# FMCWRadarv2.net
KiCad netlist of a schematic drawn in EAGLE
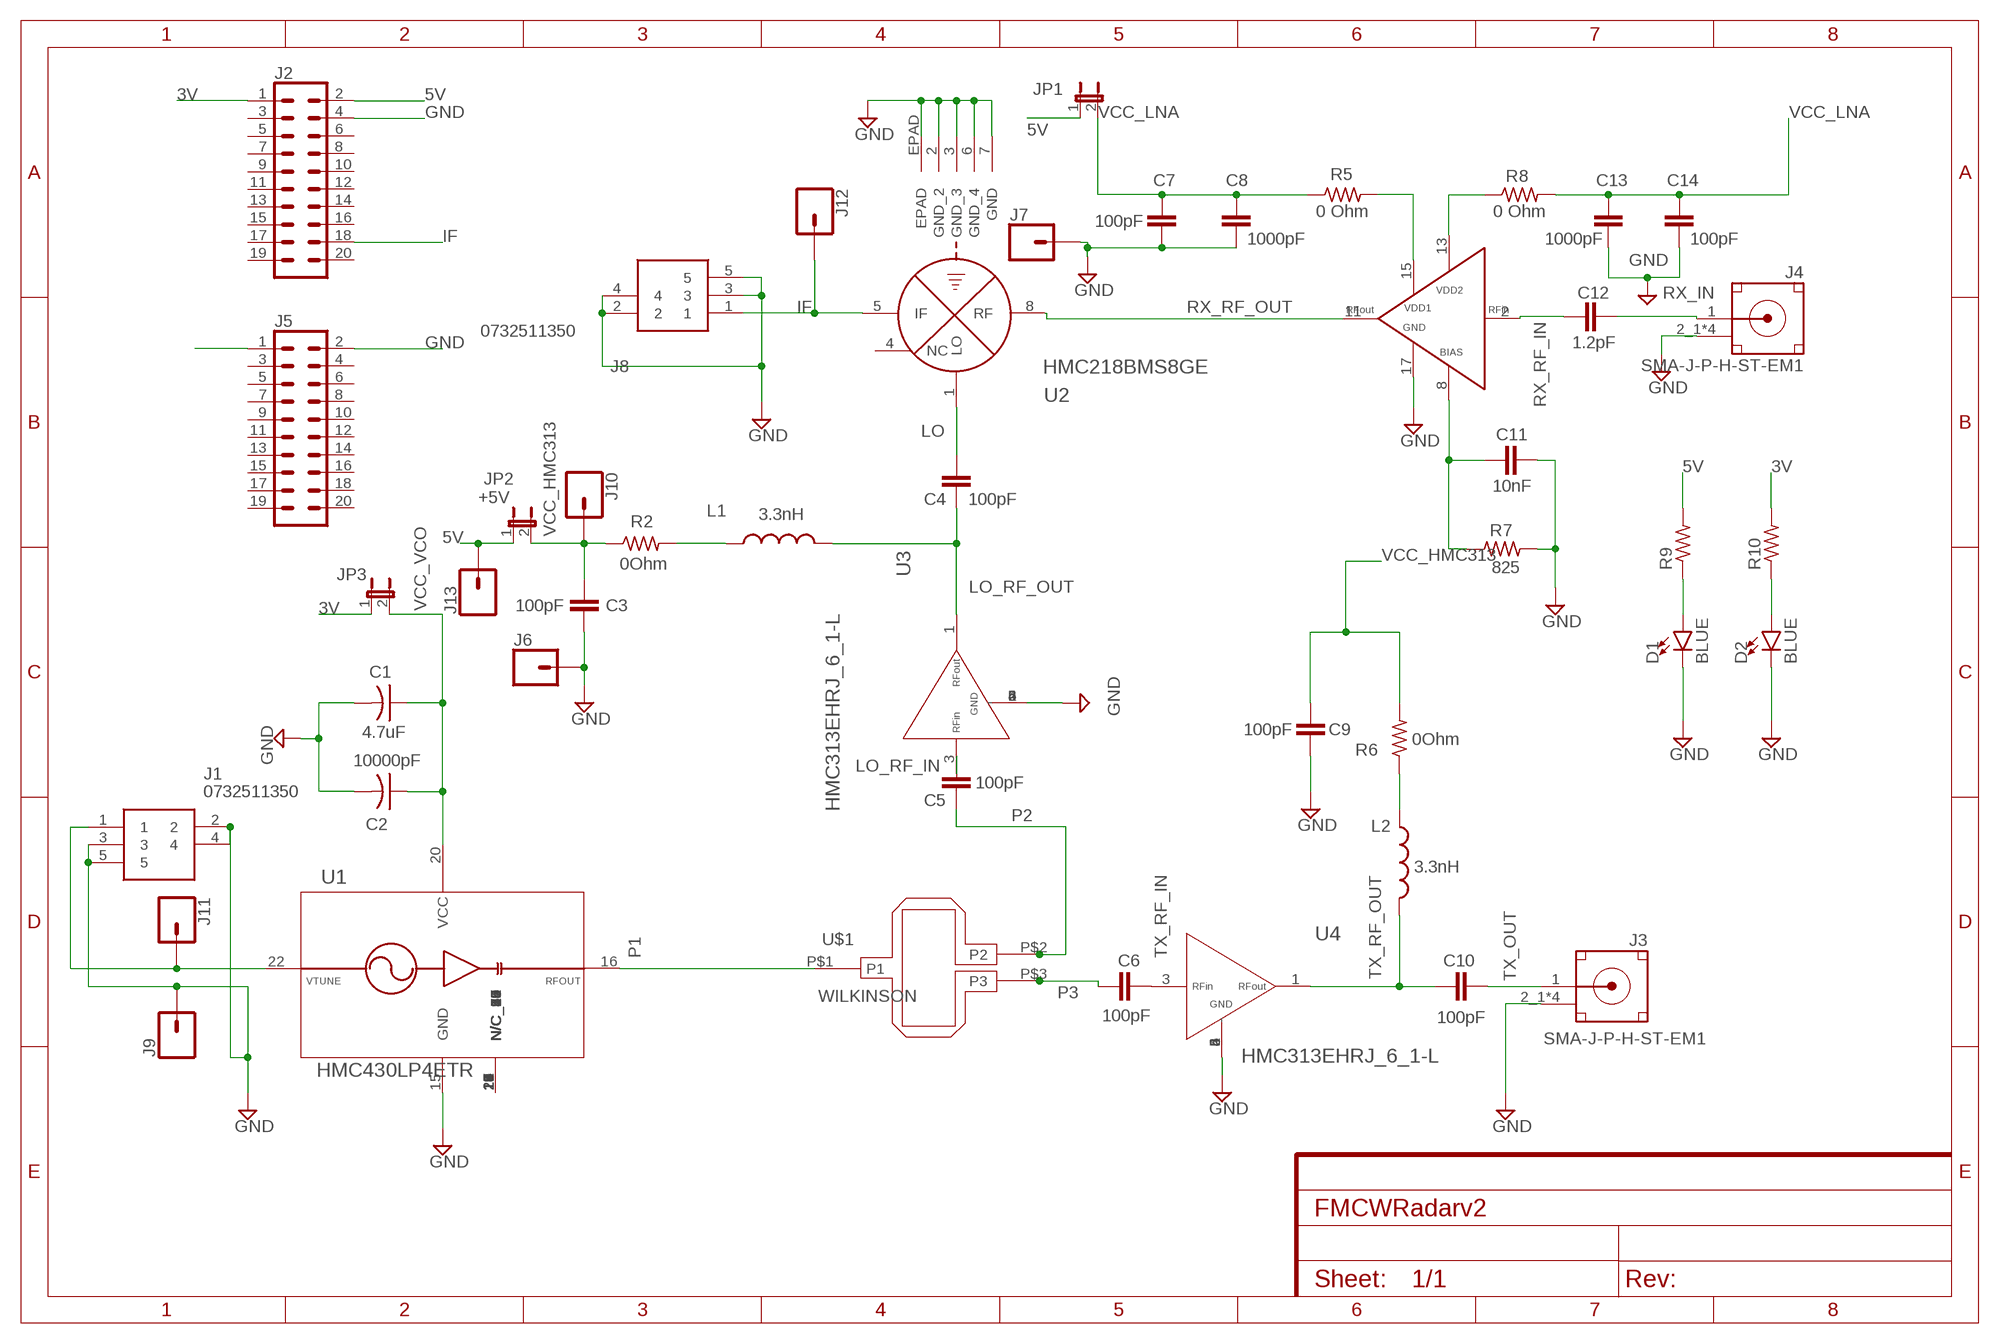
[diagram p0: schematic, sheet 1]

(export (version "E")
  (design (tool "Eeschema 10.0.6"))
  (components
    (comp (ref "C1")
      (value "4.7uF")
      (footprint "eagle-import:C0805")
      (libsource (lib "eagle-import") (part "C-USC0805"))
    )
    (comp (ref "C2")
      (value "10000pF")
      (footprint "eagle-import:C0603")
      (libsource (lib "eagle-import") (part "C-USC0603"))
    )
    (comp (ref "C3")
      (value "100pF")
      (footprint "eagle-import:C0805")
      (libsource (lib "eagle-import") (part "C-EUC0805"))
    )
    (comp (ref "C4")
      (value "100pF")
      (footprint "eagle-import:C0402")
      (libsource (lib "eagle-import") (part "C-EUC0402"))
    )
    (comp (ref "C5")
      (value "100pF")
      (footprint "eagle-import:C0402")
      (libsource (lib "eagle-import") (part "C-EUC0402"))
    )
    (comp (ref "C6")
      (value "100pF")
      (footprint "eagle-import:C0402")
      (libsource (lib "eagle-import") (part "C-EUC0402"))
    )
    (comp (ref "C7")
      (value "100pF")
      (footprint "eagle-import:C0603")
      (libsource (lib "eagle-import") (part "C-EUC0603"))
    )
    (comp (ref "C8")
      (value "1000pF")
      (footprint "eagle-import:C0603")
      (libsource (lib "eagle-import") (part "C-EUC0603"))
    )
    (comp (ref "C9")
      (value "100pF")
      (footprint "eagle-import:C0805")
      (libsource (lib "eagle-import") (part "C-EUC0805"))
    )
    (comp (ref "C10")
      (value "100pF")
      (footprint "eagle-import:C0402")
      (libsource (lib "eagle-import") (part "C-EUC0402"))
    )
    (comp (ref "C11")
      (value "10nF")
      (footprint "eagle-import:C0402")
      (libsource (lib "eagle-import") (part "C-EUC0402"))
    )
    (comp (ref "C12")
      (value "1.2pF")
      (footprint "eagle-import:C0402")
      (libsource (lib "eagle-import") (part "C-EUC0402"))
    )
    (comp (ref "C13")
      (value "1000pF")
      (footprint "eagle-import:C0603")
      (libsource (lib "eagle-import") (part "C-EUC0603"))
    )
    (comp (ref "C14")
      (value "100pF")
      (footprint "eagle-import:C0603")
      (libsource (lib "eagle-import") (part "C-EUC0603"))
    )
    (comp (ref "D1")
      (value "BLUE")
      (footprint "eagle-import:LED-1206")
      (libsource (lib "eagle-import") (part "LED-BLUE1206"))
    )
    (comp (ref "D2")
      (value "BLUE")
      (footprint "eagle-import:LED-1206")
      (libsource (lib "eagle-import") (part "LED-BLUE1206"))
    )
    (comp (ref "J1")
      (value "0732511350")
      (footprint "eagle-import:0732511350")
      (libsource (lib "eagle-import") (part "0732511350"))
    )
    (comp (ref "J2")
      (value "CONN_10X2")
      (footprint "eagle-import:2X10")
      (libsource (lib "eagle-import") (part "CONN_10X2"))
    )
    (comp (ref "J3")
      (value "SMA-J-P-H-ST-EM1")
      (footprint "eagle-import:SMA-J-P-H-ST-EM1")
      (fields (field (name "DIGI-KEY_PART_NUMBER") "SAM8857-ND") (field (name "MF") "Samtec"))
      (libsource (lib "eagle-import") (part "SMA-J-P-H-ST-EM1"))
    )
    (comp (ref "J4")
      (value "SMA-J-P-H-ST-EM1")
      (footprint "eagle-import:SMA-J-P-H-ST-EM1")
      (fields (field (name "DIGI-KEY_PART_NUMBER") "SAM8857-ND") (field (name "MF") "Samtec"))
      (libsource (lib "eagle-import") (part "SMA-J-P-H-ST-EM1"))
    )
    (comp (ref "J5")
      (value "CONN_10X2")
      (footprint "eagle-import:2X10")
      (libsource (lib "eagle-import") (part "CONN_10X2"))
    )
    (comp (ref "J6")
      (value "CONN_01")
      (footprint "eagle-import:1X01")
      (libsource (lib "eagle-import") (part "CONN_01"))
    )
    (comp (ref "J7")
      (value "CONN_01")
      (footprint "eagle-import:1X01")
      (libsource (lib "eagle-import") (part "CONN_01"))
    )
    (comp (ref "J8")
      (value "0732511350")
      (footprint "eagle-import:0732511350")
      (libsource (lib "eagle-import") (part "0732511350"))
    )
    (comp (ref "J9")
      (value "CONN_01")
      (footprint "eagle-import:1X01")
      (libsource (lib "eagle-import") (part "CONN_01"))
    )
    (comp (ref "J10")
      (value "CONN_01")
      (footprint "eagle-import:1X01")
      (libsource (lib "eagle-import") (part "CONN_01"))
    )
    (comp (ref "J11")
      (value "CONN_01")
      (footprint "eagle-import:1X01")
      (libsource (lib "eagle-import") (part "CONN_01"))
    )
    (comp (ref "J12")
      (value "CONN_01")
      (footprint "eagle-import:1X01")
      (libsource (lib "eagle-import") (part "CONN_01"))
    )
    (comp (ref "J13")
      (value "CONN_01")
      (footprint "eagle-import:1X01")
      (libsource (lib "eagle-import") (part "CONN_01"))
    )
    (comp (ref "JP1")
      (value "+5V")
      (footprint "eagle-import:JP1M")
      (libsource (lib "eagle-import") (part "JP1M"))
    )
    (comp (ref "JP2")
      (value "+5V")
      (footprint "eagle-import:JP1M")
      (libsource (lib "eagle-import") (part "JP1M"))
    )
    (comp (ref "JP3")
      (value "+5V")
      (footprint "eagle-import:JP1M")
      (libsource (lib "eagle-import") (part "JP1M"))
    )
    (comp (ref "L1")
      (value "3.3nH")
      (footprint "eagle-import:L0805")
      (libsource (lib "eagle-import") (part "L-USL0805"))
    )
    (comp (ref "L2")
      (value "3.3nH")
      (footprint "eagle-import:L0805")
      (libsource (lib "eagle-import") (part "L-USL0805"))
    )
    (comp (ref "R2")
      (value "0Ohm")
      (footprint "eagle-import:R0805")
      (libsource (lib "eagle-import") (part "R-US_R0805"))
    )
    (comp (ref "R5")
      (value "0 Ohm")
      (footprint "eagle-import:R0402")
      (libsource (lib "eagle-import") (part "R-US_R0402"))
    )
    (comp (ref "R6")
      (value "0Ohm")
      (footprint "eagle-import:R0805")
      (libsource (lib "eagle-import") (part "R-US_R0805"))
    )
    (comp (ref "R7")
      (value "825")
      (footprint "eagle-import:R0402")
      (libsource (lib "eagle-import") (part "R-US_R0402"))
    )
    (comp (ref "R8")
      (value "0 Ohm")
      (footprint "eagle-import:R0402")
      (libsource (lib "eagle-import") (part "R-US_R0402"))
    )
    (comp (ref "R9")
      (value "R-US_R0805")
      (footprint "eagle-import:R0805")
      (libsource (lib "eagle-import") (part "R-US_R0805"))
    )
    (comp (ref "R10")
      (value "R-US_R0805")
      (footprint "eagle-import:R0805")
      (libsource (lib "eagle-import") (part "R-US_R0805"))
    )
    (comp (ref "U$1")
      (value "WILKINSON")
      (footprint "eagle-import:WILKINSON")
      (libsource (lib "eagle-import") (part "WILKINSON"))
    )
    (comp (ref "U1")
      (value "HMC430LP4ETR")
      (footprint "eagle-import:SMT_24")
      (libsource (lib "eagle-import") (part "HMC430LP4ETR"))
    )
    (comp (ref "U2")
      (value "HMC218BMS8GE")
      (footprint "eagle-import:HRH_8_1")
      (libsource (lib "eagle-import") (part "HMC218BMS8GE"))
    )
    (comp (ref "U3")
      (value "HMC313EHRJ_6_1-L")
      (footprint "eagle-import:HRJ_6_1-L")
      (fields (field (name "MANUFACTURER_PART_NUMBER") "HMC313E"))
      (libsource (lib "eagle-import") (part "HMC313EHRJ_6_1-L"))
    )
    (comp (ref "U4")
      (value "HMC313EHRJ_6_1-L")
      (footprint "eagle-import:HRJ_6_1-L")
      (fields (field (name "MANUFACTURER_PART_NUMBER") "HMC313E"))
      (libsource (lib "eagle-import") (part "HMC313EHRJ_6_1-L"))
    )
    (comp (ref "U5")
      (value "HMC717ALP3E")
      (footprint "eagle-import:QFN50P300X300X100-17N")
      (libsource (lib "eagle-import") (part "HMC717ALP3E"))
    )
  )
  (nets
    (net (code "1") (name "/3V") (class "Default")
      (node (ref "J2") (pin "1") (pinfunction "1_1") (pintype "passive"))
      (node (ref "JP3") (pin "1") (pinfunction "1_1") (pintype "passive"))
      (node (ref "R10") (pin "2") (pinfunction "2_2") (pintype "passive"))
    )
    (net (code "2") (name "/5V") (class "Default")
      (node (ref "J13") (pin "1") (pinfunction "1_1") (pintype "passive"))
      (node (ref "J2") (pin "2") (pinfunction "2_2") (pintype "passive"))
      (node (ref "JP1") (pin "1") (pinfunction "1_1") (pintype "passive"))
      (node (ref "JP2") (pin "1") (pinfunction "1_1") (pintype "passive"))
      (node (ref "R9") (pin "2") (pinfunction "2_2") (pintype "passive"))
    )
    (net (code "3") (name "/IF") (class "Default")
      (node (ref "J12") (pin "1") (pinfunction "1_1") (pintype "passive"))
      (node (ref "J2") (pin "18") (pinfunction "18_18") (pintype "passive"))
      (node (ref "J8") (pin "1") (pinfunction "1_1") (pintype "bidirectional"))
      (node (ref "U2") (pin "5") (pinfunction "IF_5") (pintype "passive"))
    )
    (net (code "4") (name "/LO") (class "Default")
      (node (ref "C4") (pin "2") (pinfunction "2_2") (pintype "passive"))
      (node (ref "U2") (pin "1") (pinfunction "LO_1") (pintype "passive"))
    )
    (net (code "5") (name "/LO_RF_IN") (class "Default")
      (node (ref "C5") (pin "2") (pinfunction "2_2") (pintype "passive"))
      (node (ref "U3") (pin "3") (pinfunction "RFIN_3") (pintype "passive"))
    )
    (net (code "6") (name "/LO_RF_OUT") (class "Default")
      (node (ref "C4") (pin "1") (pinfunction "1_1") (pintype "passive"))
      (node (ref "L1") (pin "2") (pinfunction "2_2") (pintype "passive"))
      (node (ref "U3") (pin "1") (pinfunction "RFOUT_1") (pintype "passive"))
    )
    (net (code "7") (name "/P1") (class "Default")
      (node (ref "U$1") (pin "P$1") (pinfunction "P1_P$1") (pintype "bidirectional"))
      (node (ref "U1") (pin "16") (pinfunction "RFOUT_16") (pintype "output"))
    )
    (net (code "8") (name "/P2") (class "Default")
      (node (ref "C5") (pin "1") (pinfunction "1_1") (pintype "passive"))
      (node (ref "U$1") (pin "P$2") (pinfunction "P2_P$2") (pintype "bidirectional"))
    )
    (net (code "9") (name "/P3") (class "Default")
      (node (ref "C6") (pin "1") (pinfunction "1_1") (pintype "passive"))
      (node (ref "U$1") (pin "P$3") (pinfunction "P3_P$3") (pintype "bidirectional"))
    )
    (net (code "10") (name "/RX_IN") (class "Default")
      (node (ref "C12") (pin "1") (pinfunction "1_1") (pintype "passive"))
      (node (ref "J4") (pin "1") (pinfunction "SIGNAL_1") (pintype "passive"))
    )
    (net (code "11") (name "/RX_RF_IN") (class "Default")
      (node (ref "C12") (pin "2") (pinfunction "2_2") (pintype "passive"))
      (node (ref "U5") (pin "2") (pinfunction "RFIN_2") (pintype "bidirectional"))
    )
    (net (code "12") (name "/RX_RF_OUT") (class "Default")
      (node (ref "U2") (pin "8") (pinfunction "RF_8") (pintype "passive"))
      (node (ref "U5") (pin "11") (pinfunction "RFOUT_11") (pintype "bidirectional"))
    )
    (net (code "13") (name "/TX_OUT") (class "Default")
      (node (ref "C10") (pin "2") (pinfunction "2_2") (pintype "passive"))
      (node (ref "J3") (pin "1") (pinfunction "SIGNAL_1") (pintype "passive"))
    )
    (net (code "15") (name "/TX_RF_OUT") (class "Default")
      (node (ref "C10") (pin "1") (pinfunction "1_1") (pintype "passive"))
      (node (ref "L2") (pin "2") (pinfunction "2_2") (pintype "passive"))
      (node (ref "U4") (pin "1") (pinfunction "RFOUT_1") (pintype "passive"))
    )
    (net (code "16") (name "/VCC_HMC313") (class "Default")
      (node (ref "C3") (pin "1") (pinfunction "1_1") (pintype "passive"))
      (node (ref "C9") (pin "1") (pinfunction "1_1") (pintype "passive"))
      (node (ref "J10") (pin "1") (pinfunction "1_1") (pintype "passive"))
      (node (ref "JP2") (pin "2") (pinfunction "2_2") (pintype "passive"))
      (node (ref "R2") (pin "1") (pinfunction "1_1") (pintype "passive"))
      (node (ref "R6") (pin "2") (pinfunction "2_2") (pintype "passive"))
    )
    (net (code "17") (name "/VCC_LNA") (class "Default")
      (node (ref "C13") (pin "1") (pinfunction "1_1") (pintype "passive"))
      (node (ref "C14") (pin "1") (pinfunction "1_1") (pintype "passive"))
      (node (ref "C7") (pin "1") (pinfunction "1_1") (pintype "passive"))
      (node (ref "C8") (pin "1") (pinfunction "1_1") (pintype "passive"))
      (node (ref "JP1") (pin "2") (pinfunction "2_2") (pintype "passive"))
      (node (ref "R5") (pin "1") (pinfunction "1_1") (pintype "passive"))
      (node (ref "R8") (pin "2") (pinfunction "2_2") (pintype "passive"))
    )
    (net (code "18") (name "/VCC_VCO") (class "Default")
      (node (ref "C1") (pin "1") (pinfunction "1_1") (pintype "passive"))
      (node (ref "C2") (pin "1") (pinfunction "1_1") (pintype "passive"))
      (node (ref "JP3") (pin "2") (pinfunction "2_2") (pintype "passive"))
      (node (ref "U1") (pin "20") (pinfunction "VCC_20") (pintype "power_in"))
    )
    (net (code "19") (name "GND") (class "Default")
      (node (ref "C1") (pin "2") (pinfunction "2_2") (pintype "passive"))
      (node (ref "C11") (pin "1") (pinfunction "1_1") (pintype "passive"))
      (node (ref "C13") (pin "2") (pinfunction "2_2") (pintype "passive"))
      (node (ref "C14") (pin "2") (pinfunction "2_2") (pintype "passive"))
      (node (ref "C2") (pin "2") (pinfunction "2_2") (pintype "passive"))
      (node (ref "C3") (pin "2") (pinfunction "2_2") (pintype "passive"))
      (node (ref "C7") (pin "2") (pinfunction "2_2") (pintype "passive"))
      (node (ref "C8") (pin "2") (pinfunction "2_2") (pintype "passive"))
      (node (ref "C9") (pin "2") (pinfunction "2_2") (pintype "passive"))
      (node (ref "D1") (pin "C") (pinfunction "C_C") (pintype "passive"))
      (node (ref "D2") (pin "C") (pinfunction "C_C") (pintype "passive"))
      (node (ref "J1") (pin "2") (pinfunction "2_2") (pintype "bidirectional"))
      (node (ref "J1") (pin "3") (pinfunction "3_3") (pintype "bidirectional"))
      (node (ref "J1") (pin "4") (pinfunction "4_4") (pintype "bidirectional"))
      (node (ref "J1") (pin "5") (pinfunction "5_5") (pintype "bidirectional"))
      (node (ref "J2") (pin "4") (pinfunction "4_4") (pintype "passive"))
      (node (ref "J3") (pin "2_1") (pinfunction "GND_2_1") (pintype "power_in"))
      (node (ref "J3") (pin "2_2") (pinfunction "GND_2_2") (pintype "power_in"))
      (node (ref "J3") (pin "3_1") (pinfunction "GND_3_1") (pintype "power_in"))
      (node (ref "J3") (pin "3_2") (pinfunction "GND_3_2") (pintype "power_in"))
      (node (ref "J4") (pin "2_1") (pinfunction "GND_2_1") (pintype "power_in"))
      (node (ref "J4") (pin "2_2") (pinfunction "GND_2_2") (pintype "power_in"))
      (node (ref "J4") (pin "3_1") (pinfunction "GND_3_1") (pintype "power_in"))
      (node (ref "J4") (pin "3_2") (pinfunction "GND_3_2") (pintype "power_in"))
      (node (ref "J5") (pin "2") (pinfunction "2_2") (pintype "passive"))
      (node (ref "J6") (pin "1") (pinfunction "1_1") (pintype "passive"))
      (node (ref "J7") (pin "1") (pinfunction "1_1") (pintype "passive"))
      (node (ref "J8") (pin "2") (pinfunction "2_2") (pintype "bidirectional"))
      (node (ref "J8") (pin "3") (pinfunction "3_3") (pintype "bidirectional"))
      (node (ref "J8") (pin "4") (pinfunction "4_4") (pintype "bidirectional"))
      (node (ref "J8") (pin "5") (pinfunction "5_5") (pintype "bidirectional"))
      (node (ref "J9") (pin "1") (pinfunction "1_1") (pintype "passive"))
      (node (ref "R7") (pin "2") (pinfunction "2_2") (pintype "passive"))
      (node (ref "U1") (pin "15") (pinfunction "GND_15") (pintype "passive"))
      (node (ref "U2") (pin "2") (pinfunction "GND_2_2") (pintype "passive"))
      (node (ref "U2") (pin "3") (pinfunction "GND_3_3") (pintype "passive"))
      (node (ref "U2") (pin "6") (pinfunction "GND_4_6") (pintype "passive"))
      (node (ref "U2") (pin "7") (pinfunction "GND_7") (pintype "passive"))
      (node (ref "U2") (pin "EPAD") (pinfunction "EPAD_EPAD") (pintype "passive"))
      (node (ref "U3") (pin "2") (pinfunction "GND_2_2") (pintype "passive"))
      (node (ref "U3") (pin "4") (pinfunction "GND_3_4") (pintype "passive"))
      (node (ref "U3") (pin "5") (pinfunction "GND_4_5") (pintype "passive"))
      (node (ref "U3") (pin "6") (pinfunction "GND_6") (pintype "passive"))
      (node (ref "U4") (pin "2") (pinfunction "GND_2_2") (pintype "passive"))
      (node (ref "U4") (pin "4") (pinfunction "GND_3_4") (pintype "passive"))
      (node (ref "U4") (pin "5") (pinfunction "GND_4_5") (pintype "passive"))
      (node (ref "U4") (pin "6") (pinfunction "GND_6") (pintype "passive"))
      (node (ref "U5") (pin "17") (pinfunction "GND_17") (pintype "bidirectional"))
    )
    (net (code "20") (name "Net-(D1-PadA)") (class "Default")
      (node (ref "D1") (pin "A") (pinfunction "A_A") (pintype "passive"))
      (node (ref "R9") (pin "1") (pinfunction "1_1") (pintype "passive"))
    )
    (net (code "21") (name "Net-(D2-PadA)") (class "Default")
      (node (ref "D2") (pin "A") (pinfunction "A_A") (pintype "passive"))
      (node (ref "R10") (pin "1") (pinfunction "1_1") (pintype "passive"))
    )
    (net (code "22") (name "Net-(L1-Pad1)") (class "Default")
      (node (ref "L1") (pin "1") (pinfunction "1_1") (pintype "passive"))
      (node (ref "R2") (pin "2") (pinfunction "2_2") (pintype "passive"))
    )
    (net (code "23") (name "Net-(L2-Pad1)") (class "Default")
      (node (ref "L2") (pin "1") (pinfunction "1_1") (pintype "passive"))
      (node (ref "R6") (pin "1") (pinfunction "1_1") (pintype "passive"))
    )
    (net (code "24") (name "Net-(U1-VTUNE)") (class "Default")
      (node (ref "J1") (pin "1") (pinfunction "1_1") (pintype "bidirectional"))
      (node (ref "J11") (pin "1") (pinfunction "1_1") (pintype "passive"))
      (node (ref "U1") (pin "22") (pinfunction "VTUNE_22") (pintype "passive"))
    )
    (net (code "25") (name "Net-(U4-RFIN)") (class "Default")
      (node (ref "C6") (pin "2") (pinfunction "2_2") (pintype "passive"))
      (node (ref "U4") (pin "3") (pinfunction "RFIN_3") (pintype "passive"))
    )
    (net (code "26") (name "Net-(U5-BIAS)") (class "Default")
      (node (ref "C11") (pin "2") (pinfunction "2_2") (pintype "passive"))
      (node (ref "R7") (pin "1") (pinfunction "1_1") (pintype "passive"))
      (node (ref "U5") (pin "8") (pinfunction "BIAS_8") (pintype "bidirectional"))
    )
    (net (code "27") (name "Net-(U5-VDD1)") (class "Default")
      (node (ref "R5") (pin "2") (pinfunction "2_2") (pintype "passive"))
      (node (ref "U5") (pin "15") (pinfunction "VDD1_15") (pintype "bidirectional"))
    )
    (net (code "28") (name "Net-(U5-VDD2)") (class "Default")
      (node (ref "R8") (pin "1") (pinfunction "1_1") (pintype "passive"))
      (node (ref "U5") (pin "13") (pinfunction "VDD2_13") (pintype "bidirectional"))
    )
    (net (code "29") (name "unconnected-(J2-Pad3)") (class "Default")
      (node (ref "J2") (pin "3") (pinfunction "3_3") (pintype "passive"))
    )
    (net (code "30") (name "unconnected-(J2-Pad5)") (class "Default")
      (node (ref "J2") (pin "5") (pinfunction "5_5") (pintype "passive"))
    )
    (net (code "31") (name "unconnected-(J2-Pad6)") (class "Default")
      (node (ref "J2") (pin "6") (pinfunction "6_6") (pintype "passive"))
    )
    (net (code "32") (name "unconnected-(J2-Pad7)") (class "Default")
      (node (ref "J2") (pin "7") (pinfunction "7_7") (pintype "passive"))
    )
    (net (code "33") (name "unconnected-(J2-Pad8)") (class "Default")
      (node (ref "J2") (pin "8") (pinfunction "8_8") (pintype "passive"))
    )
    (net (code "34") (name "unconnected-(J2-Pad9)") (class "Default")
      (node (ref "J2") (pin "9") (pinfunction "9_9") (pintype "passive"))
    )
    (net (code "35") (name "unconnected-(J2-Pad10)") (class "Default")
      (node (ref "J2") (pin "10") (pinfunction "10_10") (pintype "passive"))
    )
    (net (code "36") (name "unconnected-(J2-Pad11)") (class "Default")
      (node (ref "J2") (pin "11") (pinfunction "11_11") (pintype "passive"))
    )
    (net (code "37") (name "unconnected-(J2-Pad12)") (class "Default")
      (node (ref "J2") (pin "12") (pinfunction "12_12") (pintype "passive"))
    )
    (net (code "38") (name "unconnected-(J2-Pad13)") (class "Default")
      (node (ref "J2") (pin "13") (pinfunction "13_13") (pintype "passive"))
    )
    (net (code "39") (name "unconnected-(J2-Pad14)") (class "Default")
      (node (ref "J2") (pin "14") (pinfunction "14_14") (pintype "passive"))
    )
    (net (code "40") (name "unconnected-(J2-Pad15)") (class "Default")
      (node (ref "J2") (pin "15") (pinfunction "15_15") (pintype "passive"))
    )
    (net (code "41") (name "unconnected-(J2-Pad16)") (class "Default")
      (node (ref "J2") (pin "16") (pinfunction "16_16") (pintype "passive"))
    )
    (net (code "42") (name "unconnected-(J2-Pad17)") (class "Default")
      (node (ref "J2") (pin "17") (pinfunction "17_17") (pintype "passive"))
    )
    (net (code "43") (name "unconnected-(J2-Pad19)") (class "Default")
      (node (ref "J2") (pin "19") (pinfunction "19_19") (pintype "passive"))
    )
    (net (code "44") (name "unconnected-(J2-Pad20)") (class "Default")
      (node (ref "J2") (pin "20") (pinfunction "20_20") (pintype "passive"))
    )
    (net (code "45") (name "unconnected-(J5-Pad1)") (class "Default")
      (node (ref "J5") (pin "1") (pinfunction "1_1") (pintype "passive"))
    )
    (net (code "46") (name "unconnected-(J5-Pad3)") (class "Default")
      (node (ref "J5") (pin "3") (pinfunction "3_3") (pintype "passive"))
    )
    (net (code "47") (name "unconnected-(J5-Pad4)") (class "Default")
      (node (ref "J5") (pin "4") (pinfunction "4_4") (pintype "passive"))
    )
    (net (code "48") (name "unconnected-(J5-Pad5)") (class "Default")
      (node (ref "J5") (pin "5") (pinfunction "5_5") (pintype "passive"))
    )
    (net (code "49") (name "unconnected-(J5-Pad6)") (class "Default")
      (node (ref "J5") (pin "6") (pinfunction "6_6") (pintype "passive"))
    )
    (net (code "50") (name "unconnected-(J5-Pad7)") (class "Default")
      (node (ref "J5") (pin "7") (pinfunction "7_7") (pintype "passive"))
    )
    (net (code "51") (name "unconnected-(J5-Pad8)") (class "Default")
      (node (ref "J5") (pin "8") (pinfunction "8_8") (pintype "passive"))
    )
    (net (code "52") (name "unconnected-(J5-Pad9)") (class "Default")
      (node (ref "J5") (pin "9") (pinfunction "9_9") (pintype "passive"))
    )
    (net (code "53") (name "unconnected-(J5-Pad10)") (class "Default")
      (node (ref "J5") (pin "10") (pinfunction "10_10") (pintype "passive"))
    )
    (net (code "54") (name "unconnected-(J5-Pad11)") (class "Default")
      (node (ref "J5") (pin "11") (pinfunction "11_11") (pintype "passive"))
    )
    (net (code "55") (name "unconnected-(J5-Pad12)") (class "Default")
      (node (ref "J5") (pin "12") (pinfunction "12_12") (pintype "passive"))
    )
    (net (code "56") (name "unconnected-(J5-Pad13)") (class "Default")
      (node (ref "J5") (pin "13") (pinfunction "13_13") (pintype "passive"))
    )
    (net (code "57") (name "unconnected-(J5-Pad14)") (class "Default")
      (node (ref "J5") (pin "14") (pinfunction "14_14") (pintype "passive"))
    )
    (net (code "58") (name "unconnected-(J5-Pad15)") (class "Default")
      (node (ref "J5") (pin "15") (pinfunction "15_15") (pintype "passive"))
    )
    (net (code "59") (name "unconnected-(J5-Pad16)") (class "Default")
      (node (ref "J5") (pin "16") (pinfunction "16_16") (pintype "passive"))
    )
    (net (code "60") (name "unconnected-(J5-Pad17)") (class "Default")
      (node (ref "J5") (pin "17") (pinfunction "17_17") (pintype "passive"))
    )
    (net (code "61") (name "unconnected-(J5-Pad18)") (class "Default")
      (node (ref "J5") (pin "18") (pinfunction "18_18") (pintype "passive"))
    )
    (net (code "62") (name "unconnected-(J5-Pad19)") (class "Default")
      (node (ref "J5") (pin "19") (pinfunction "19_19") (pintype "passive"))
    )
    (net (code "63") (name "unconnected-(J5-Pad20)") (class "Default")
      (node (ref "J5") (pin "20") (pinfunction "20_20") (pintype "passive"))
    )
    (net (code "64") (name "unconnected-(U1-N{slash}C-Pad24)") (class "Default")
      (node (ref "U1") (pin "24") (pinfunction "N/C_24") (pintype "no_connect"))
    )
    (net (code "65") (name "unconnected-(U1-N{slash}C_2-Pad1)") (class "Default")
      (node (ref "U1") (pin "1") (pinfunction "N/C_2_1") (pintype "no_connect"))
    )
    (net (code "66") (name "unconnected-(U1-N{slash}C_3-Pad2)") (class "Default")
      (node (ref "U1") (pin "2") (pinfunction "N/C_3_2") (pintype "no_connect"))
    )
    (net (code "67") (name "unconnected-(U1-N{slash}C_4-Pad3)") (class "Default")
      (node (ref "U1") (pin "3") (pinfunction "N/C_4_3") (pintype "no_connect"))
    )
    (net (code "68") (name "unconnected-(U1-N{slash}C_5-Pad4)") (class "Default")
      (node (ref "U1") (pin "4") (pinfunction "N/C_5_4") (pintype "no_connect"))
    )
    (net (code "69") (name "unconnected-(U1-N{slash}C_6-Pad5)") (class "Default")
      (node (ref "U1") (pin "5") (pinfunction "N/C_6_5") (pintype "no_connect"))
    )
    (net (code "70") (name "unconnected-(U1-N{slash}C_7-Pad6)") (class "Default")
      (node (ref "U1") (pin "6") (pinfunction "N/C_7_6") (pintype "no_connect"))
    )
    (net (code "71") (name "unconnected-(U1-N{slash}C_8-Pad7)") (class "Default")
      (node (ref "U1") (pin "7") (pinfunction "N/C_8_7") (pintype "no_connect"))
    )
    (net (code "72") (name "unconnected-(U1-N{slash}C_9-Pad8)") (class "Default")
      (node (ref "U1") (pin "8") (pinfunction "N/C_9_8") (pintype "no_connect"))
    )
    (net (code "73") (name "unconnected-(U1-N{slash}C_10-Pad9)") (class "Default")
      (node (ref "U1") (pin "9") (pinfunction "N/C_10_9") (pintype "no_connect"))
    )
    (net (code "74") (name "unconnected-(U1-N{slash}C_11-Pad10)") (class "Default")
      (node (ref "U1") (pin "10") (pinfunction "N/C_11_10") (pintype "no_connect"))
    )
    (net (code "75") (name "unconnected-(U1-N{slash}C_12-Pad11)") (class "Default")
      (node (ref "U1") (pin "11") (pinfunction "N/C_12_11") (pintype "no_connect"))
    )
    (net (code "76") (name "unconnected-(U1-N{slash}C_13-Pad12)") (class "Default")
      (node (ref "U1") (pin "12") (pinfunction "N/C_13_12") (pintype "no_connect"))
    )
    (net (code "77") (name "unconnected-(U1-N{slash}C_14-Pad13)") (class "Default")
      (node (ref "U1") (pin "13") (pinfunction "N/C_14_13") (pintype "no_connect"))
    )
    (net (code "78") (name "unconnected-(U1-N{slash}C_15-Pad14)") (class "Default")
      (node (ref "U1") (pin "14") (pinfunction "N/C_15_14") (pintype "no_connect"))
    )
    (net (code "79") (name "unconnected-(U1-N{slash}C_16-Pad17)") (class "Default")
      (node (ref "U1") (pin "17") (pinfunction "N/C_16_17") (pintype "no_connect"))
    )
    (net (code "80") (name "unconnected-(U1-N{slash}C_17-Pad18)") (class "Default")
      (node (ref "U1") (pin "18") (pinfunction "N/C_17_18") (pintype "no_connect"))
    )
    (net (code "81") (name "unconnected-(U1-N{slash}C_18-Pad19)") (class "Default")
      (node (ref "U1") (pin "19") (pinfunction "N/C_18_19") (pintype "no_connect"))
    )
    (net (code "82") (name "unconnected-(U1-N{slash}C_19-Pad21)") (class "Default")
      (node (ref "U1") (pin "21") (pinfunction "N/C_19_21") (pintype "no_connect"))
    )
    (net (code "83") (name "unconnected-(U1-N{slash}C_20-Pad23)") (class "Default")
      (node (ref "U1") (pin "23") (pinfunction "N/C_20_23") (pintype "no_connect"))
    )
    (net (code "84") (name "unconnected-(U2-NC-Pad4)") (class "Default")
      (node (ref "U2") (pin "4") (pinfunction "NC_4") (pintype "passive"))
    )
  )
)
